# Dash_Switches.net
KiCad netlist of a schematic drawn in EAGLE
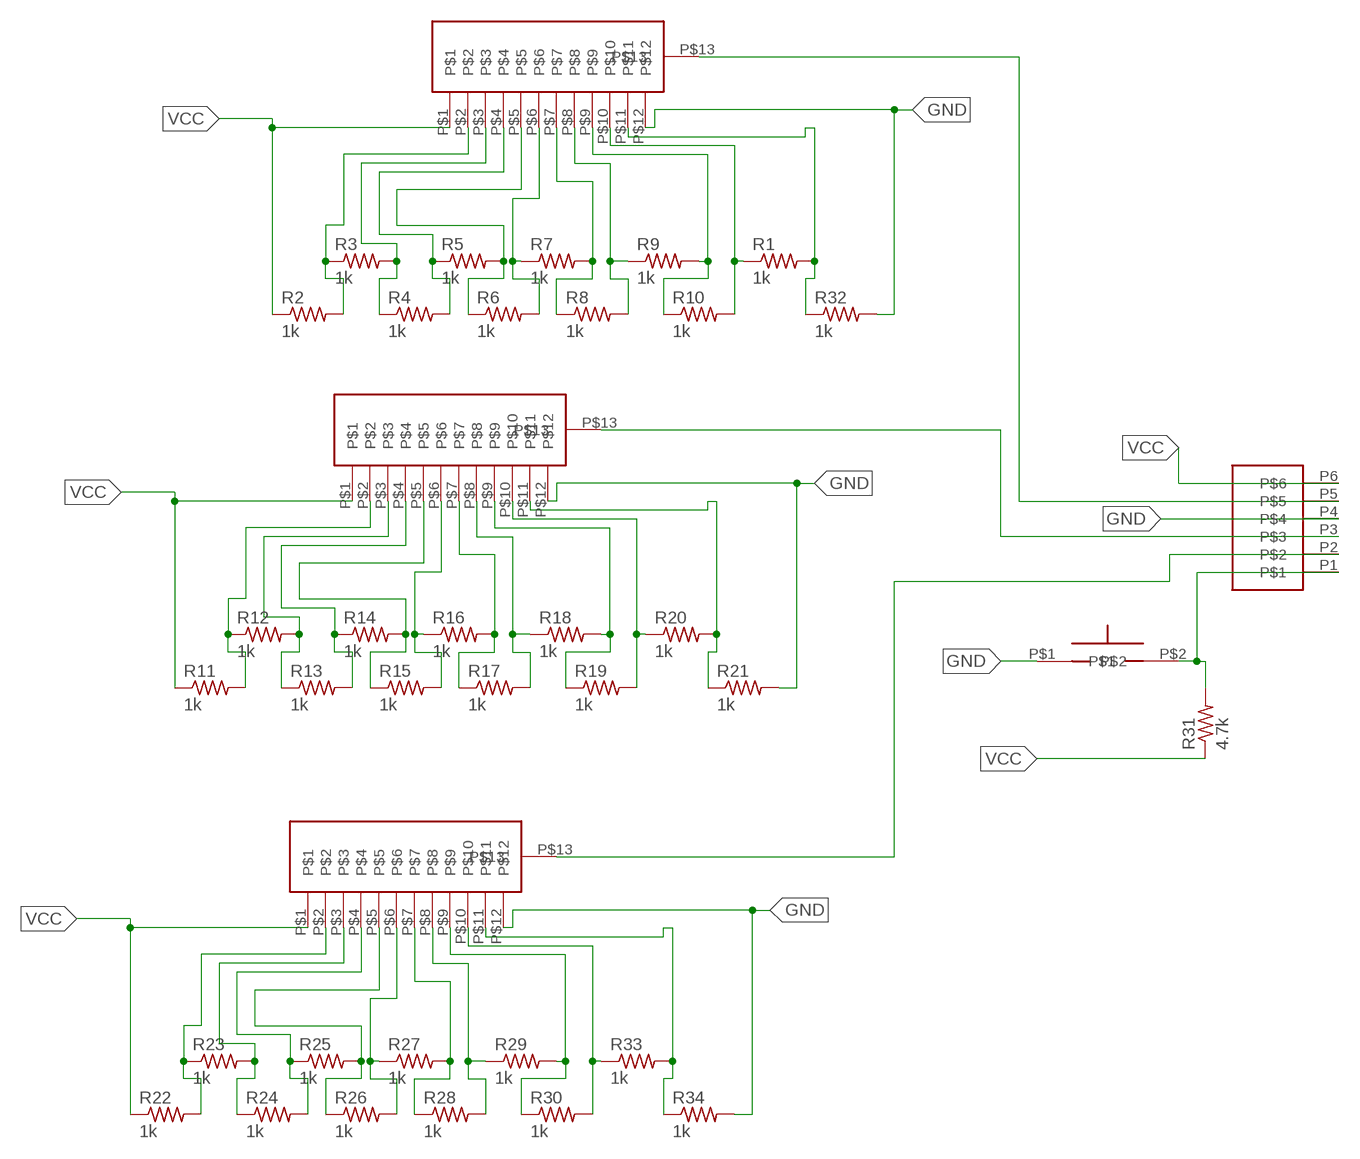
[diagram p0: schematic, sheet 1]

(export (version "E")
  (design (tool "Eeschema 10.0.6"))
  (components
    (comp (ref "R1")
      (value "1k")
      (footprint "eagle-import:R0603")
      (libsource (lib "eagle-import") (part "R-US_R0603"))
    )
    (comp (ref "R2")
      (value "1k")
      (footprint "eagle-import:R0603")
      (libsource (lib "eagle-import") (part "R-US_R0603"))
    )
    (comp (ref "R3")
      (value "1k")
      (footprint "eagle-import:R0603")
      (libsource (lib "eagle-import") (part "R-US_R0603"))
    )
    (comp (ref "R4")
      (value "1k")
      (footprint "eagle-import:R0603")
      (libsource (lib "eagle-import") (part "R-US_R0603"))
    )
    (comp (ref "R5")
      (value "1k")
      (footprint "eagle-import:R0603")
      (libsource (lib "eagle-import") (part "R-US_R0603"))
    )
    (comp (ref "R6")
      (value "1k")
      (footprint "eagle-import:R0603")
      (libsource (lib "eagle-import") (part "R-US_R0603"))
    )
    (comp (ref "R7")
      (value "1k")
      (footprint "eagle-import:R0603")
      (libsource (lib "eagle-import") (part "R-US_R0603"))
    )
    (comp (ref "R8")
      (value "1k")
      (footprint "eagle-import:R0603")
      (libsource (lib "eagle-import") (part "R-US_R0603"))
    )
    (comp (ref "R9")
      (value "1k")
      (footprint "eagle-import:R0603")
      (libsource (lib "eagle-import") (part "R-US_R0603"))
    )
    (comp (ref "R10")
      (value "1k")
      (footprint "eagle-import:R0603")
      (libsource (lib "eagle-import") (part "R-US_R0603"))
    )
    (comp (ref "R11")
      (value "1k")
      (footprint "eagle-import:R0603")
      (libsource (lib "eagle-import") (part "R-US_R0603"))
    )
    (comp (ref "R12")
      (value "1k")
      (footprint "eagle-import:R0603")
      (libsource (lib "eagle-import") (part "R-US_R0603"))
    )
    (comp (ref "R13")
      (value "1k")
      (footprint "eagle-import:R0603")
      (libsource (lib "eagle-import") (part "R-US_R0603"))
    )
    (comp (ref "R14")
      (value "1k")
      (footprint "eagle-import:R0603")
      (libsource (lib "eagle-import") (part "R-US_R0603"))
    )
    (comp (ref "R15")
      (value "1k")
      (footprint "eagle-import:R0603")
      (libsource (lib "eagle-import") (part "R-US_R0603"))
    )
    (comp (ref "R16")
      (value "1k")
      (footprint "eagle-import:R0603")
      (libsource (lib "eagle-import") (part "R-US_R0603"))
    )
    (comp (ref "R17")
      (value "1k")
      (footprint "eagle-import:R0603")
      (libsource (lib "eagle-import") (part "R-US_R0603"))
    )
    (comp (ref "R18")
      (value "1k")
      (footprint "eagle-import:R0603")
      (libsource (lib "eagle-import") (part "R-US_R0603"))
    )
    (comp (ref "R19")
      (value "1k")
      (footprint "eagle-import:R0603")
      (libsource (lib "eagle-import") (part "R-US_R0603"))
    )
    (comp (ref "R20")
      (value "1k")
      (footprint "eagle-import:R0603")
      (libsource (lib "eagle-import") (part "R-US_R0603"))
    )
    (comp (ref "R21")
      (value "1k")
      (footprint "eagle-import:R0603")
      (libsource (lib "eagle-import") (part "R-US_R0603"))
    )
    (comp (ref "R22")
      (value "1k")
      (footprint "eagle-import:R0603")
      (libsource (lib "eagle-import") (part "R-US_R0603"))
    )
    (comp (ref "R23")
      (value "1k")
      (footprint "eagle-import:R0603")
      (libsource (lib "eagle-import") (part "R-US_R0603"))
    )
    (comp (ref "R24")
      (value "1k")
      (footprint "eagle-import:R0603")
      (libsource (lib "eagle-import") (part "R-US_R0603"))
    )
    (comp (ref "R25")
      (value "1k")
      (footprint "eagle-import:R0603")
      (libsource (lib "eagle-import") (part "R-US_R0603"))
    )
    (comp (ref "R26")
      (value "1k")
      (footprint "eagle-import:R0603")
      (libsource (lib "eagle-import") (part "R-US_R0603"))
    )
    (comp (ref "R27")
      (value "1k")
      (footprint "eagle-import:R0603")
      (libsource (lib "eagle-import") (part "R-US_R0603"))
    )
    (comp (ref "R28")
      (value "1k")
      (footprint "eagle-import:R0603")
      (libsource (lib "eagle-import") (part "R-US_R0603"))
    )
    (comp (ref "R29")
      (value "1k")
      (footprint "eagle-import:R0603")
      (libsource (lib "eagle-import") (part "R-US_R0603"))
    )
    (comp (ref "R30")
      (value "1k")
      (footprint "eagle-import:R0603")
      (libsource (lib "eagle-import") (part "R-US_R0603"))
    )
    (comp (ref "R31")
      (value "4.7k")
      (footprint "eagle-import:R0603")
      (libsource (lib "eagle-import") (part "R-US_R0603"))
    )
    (comp (ref "R32")
      (value "1k")
      (footprint "eagle-import:R0603")
      (libsource (lib "eagle-import") (part "R-US_R0603"))
    )
    (comp (ref "R33")
      (value "1k")
      (footprint "eagle-import:R0603")
      (libsource (lib "eagle-import") (part "R-US_R0603"))
    )
    (comp (ref "R34")
      (value "1k")
      (footprint "eagle-import:R0603")
      (libsource (lib "eagle-import") (part "R-US_R0603"))
    )
    (comp (ref "U$1")
      (value "ROTSWITCH")
      (footprint "eagle-import:ROTSWITCH")
      (libsource (lib "eagle-import") (part "ROTSWITCH"))
    )
    (comp (ref "U$2")
      (value "ROTSWITCH")
      (footprint "eagle-import:ROTSWITCH")
      (libsource (lib "eagle-import") (part "ROTSWITCH"))
    )
    (comp (ref "U$3")
      (value "ROTSWITCH")
      (footprint "eagle-import:ROTSWITCH")
      (libsource (lib "eagle-import") (part "ROTSWITCH"))
    )
    (comp (ref "U$5")
      (value "PUSH")
      (footprint "eagle-import:PUSH")
      (libsource (lib "eagle-import") (part "PUSH"))
    )
    (comp (ref "U$6")
      (value "MICRO6LOCK")
      (footprint "eagle-import:MICRO6LOCK")
      (libsource (lib "eagle-import") (part "MICRO6LOCK"))
    )
  )
  (nets
    (net (code "1") (name "GND") (class "Default")
      (node (ref "R21") (pin "2") (pinfunction "2_2") (pintype "passive"))
      (node (ref "R32") (pin "2") (pinfunction "2_2") (pintype "passive"))
      (node (ref "R34") (pin "2") (pinfunction "2_2") (pintype "passive"))
      (node (ref "U$1") (pin "P$12") (pinfunction "P$12_P$12") (pintype "bidirectional"))
      (node (ref "U$2") (pin "P$12") (pinfunction "P$12_P$12") (pintype "bidirectional"))
      (node (ref "U$3") (pin "P$12") (pinfunction "P$12_P$12") (pintype "bidirectional"))
      (node (ref "U$5") (pin "P$1") (pinfunction "P$1_P$1") (pintype "bidirectional"))
      (node (ref "U$6") (pin "P4") (pinfunction "P$4_P4") (pintype "bidirectional"))
    )
    (net (code "2") (name "Net-(R1-Pad1)") (class "Default")
      (node (ref "R1") (pin "1") (pinfunction "1_1") (pintype "passive"))
      (node (ref "R10") (pin "2") (pinfunction "2_2") (pintype "passive"))
      (node (ref "U$1") (pin "P$10") (pinfunction "P$10_P$10") (pintype "bidirectional"))
    )
    (net (code "3") (name "Net-(R1-Pad2)") (class "Default")
      (node (ref "R1") (pin "2") (pinfunction "2_2") (pintype "passive"))
      (node (ref "R32") (pin "1") (pinfunction "1_1") (pintype "passive"))
      (node (ref "U$1") (pin "P$11") (pinfunction "P$11_P$11") (pintype "bidirectional"))
    )
    (net (code "4") (name "Net-(R2-Pad2)") (class "Default")
      (node (ref "R2") (pin "2") (pinfunction "2_2") (pintype "passive"))
      (node (ref "R3") (pin "1") (pinfunction "1_1") (pintype "passive"))
      (node (ref "U$1") (pin "P$2") (pinfunction "P$2_P$2") (pintype "bidirectional"))
    )
    (net (code "5") (name "Net-(R3-Pad2)") (class "Default")
      (node (ref "R3") (pin "2") (pinfunction "2_2") (pintype "passive"))
      (node (ref "R4") (pin "1") (pinfunction "1_1") (pintype "passive"))
      (node (ref "U$1") (pin "P$3") (pinfunction "P$3_P$3") (pintype "bidirectional"))
    )
    (net (code "6") (name "Net-(R4-Pad2)") (class "Default")
      (node (ref "R4") (pin "2") (pinfunction "2_2") (pintype "passive"))
      (node (ref "R5") (pin "1") (pinfunction "1_1") (pintype "passive"))
      (node (ref "U$1") (pin "P$4") (pinfunction "P$4_P$4") (pintype "bidirectional"))
    )
    (net (code "7") (name "Net-(R5-Pad2)") (class "Default")
      (node (ref "R5") (pin "2") (pinfunction "2_2") (pintype "passive"))
      (node (ref "R6") (pin "1") (pinfunction "1_1") (pintype "passive"))
      (node (ref "U$1") (pin "P$5") (pinfunction "P$5_P$5") (pintype "bidirectional"))
    )
    (net (code "8") (name "Net-(R6-Pad2)") (class "Default")
      (node (ref "R6") (pin "2") (pinfunction "2_2") (pintype "passive"))
      (node (ref "R7") (pin "1") (pinfunction "1_1") (pintype "passive"))
      (node (ref "U$1") (pin "P$6") (pinfunction "P$6_P$6") (pintype "bidirectional"))
    )
    (net (code "9") (name "Net-(R7-Pad2)") (class "Default")
      (node (ref "R7") (pin "2") (pinfunction "2_2") (pintype "passive"))
      (node (ref "R8") (pin "1") (pinfunction "1_1") (pintype "passive"))
      (node (ref "U$1") (pin "P$7") (pinfunction "P$7_P$7") (pintype "bidirectional"))
    )
    (net (code "10") (name "Net-(R8-Pad2)") (class "Default")
      (node (ref "R8") (pin "2") (pinfunction "2_2") (pintype "passive"))
      (node (ref "R9") (pin "1") (pinfunction "1_1") (pintype "passive"))
      (node (ref "U$1") (pin "P$8") (pinfunction "P$8_P$8") (pintype "bidirectional"))
    )
    (net (code "11") (name "Net-(R10-Pad1)") (class "Default")
      (node (ref "R10") (pin "1") (pinfunction "1_1") (pintype "passive"))
      (node (ref "R9") (pin "2") (pinfunction "2_2") (pintype "passive"))
      (node (ref "U$1") (pin "P$9") (pinfunction "P$9_P$9") (pintype "bidirectional"))
    )
    (net (code "12") (name "Net-(R11-Pad2)") (class "Default")
      (node (ref "R11") (pin "2") (pinfunction "2_2") (pintype "passive"))
      (node (ref "R12") (pin "1") (pinfunction "1_1") (pintype "passive"))
      (node (ref "U$2") (pin "P$2") (pinfunction "P$2_P$2") (pintype "bidirectional"))
    )
    (net (code "13") (name "Net-(R12-Pad2)") (class "Default")
      (node (ref "R12") (pin "2") (pinfunction "2_2") (pintype "passive"))
      (node (ref "R13") (pin "1") (pinfunction "1_1") (pintype "passive"))
      (node (ref "U$2") (pin "P$3") (pinfunction "P$3_P$3") (pintype "bidirectional"))
    )
    (net (code "14") (name "Net-(R13-Pad2)") (class "Default")
      (node (ref "R13") (pin "2") (pinfunction "2_2") (pintype "passive"))
      (node (ref "R14") (pin "1") (pinfunction "1_1") (pintype "passive"))
      (node (ref "U$2") (pin "P$4") (pinfunction "P$4_P$4") (pintype "bidirectional"))
    )
    (net (code "15") (name "Net-(R14-Pad2)") (class "Default")
      (node (ref "R14") (pin "2") (pinfunction "2_2") (pintype "passive"))
      (node (ref "R15") (pin "1") (pinfunction "1_1") (pintype "passive"))
      (node (ref "U$2") (pin "P$5") (pinfunction "P$5_P$5") (pintype "bidirectional"))
    )
    (net (code "16") (name "Net-(R15-Pad2)") (class "Default")
      (node (ref "R15") (pin "2") (pinfunction "2_2") (pintype "passive"))
      (node (ref "R16") (pin "1") (pinfunction "1_1") (pintype "passive"))
      (node (ref "U$2") (pin "P$6") (pinfunction "P$6_P$6") (pintype "bidirectional"))
    )
    (net (code "17") (name "Net-(R16-Pad2)") (class "Default")
      (node (ref "R16") (pin "2") (pinfunction "2_2") (pintype "passive"))
      (node (ref "R17") (pin "1") (pinfunction "1_1") (pintype "passive"))
      (node (ref "U$2") (pin "P$7") (pinfunction "P$7_P$7") (pintype "bidirectional"))
    )
    (net (code "18") (name "Net-(R17-Pad2)") (class "Default")
      (node (ref "R17") (pin "2") (pinfunction "2_2") (pintype "passive"))
      (node (ref "R18") (pin "1") (pinfunction "1_1") (pintype "passive"))
      (node (ref "U$2") (pin "P$8") (pinfunction "P$8_P$8") (pintype "bidirectional"))
    )
    (net (code "19") (name "Net-(R18-Pad2)") (class "Default")
      (node (ref "R18") (pin "2") (pinfunction "2_2") (pintype "passive"))
      (node (ref "R19") (pin "1") (pinfunction "1_1") (pintype "passive"))
      (node (ref "U$2") (pin "P$9") (pinfunction "P$9_P$9") (pintype "bidirectional"))
    )
    (net (code "20") (name "Net-(R19-Pad2)") (class "Default")
      (node (ref "R19") (pin "2") (pinfunction "2_2") (pintype "passive"))
      (node (ref "R20") (pin "1") (pinfunction "1_1") (pintype "passive"))
      (node (ref "U$2") (pin "P$10") (pinfunction "P$10_P$10") (pintype "bidirectional"))
    )
    (net (code "21") (name "Net-(R20-Pad2)") (class "Default")
      (node (ref "R20") (pin "2") (pinfunction "2_2") (pintype "passive"))
      (node (ref "R21") (pin "1") (pinfunction "1_1") (pintype "passive"))
      (node (ref "U$2") (pin "P$11") (pinfunction "P$11_P$11") (pintype "bidirectional"))
    )
    (net (code "22") (name "Net-(R22-Pad2)") (class "Default")
      (node (ref "R22") (pin "2") (pinfunction "2_2") (pintype "passive"))
      (node (ref "R23") (pin "1") (pinfunction "1_1") (pintype "passive"))
      (node (ref "U$3") (pin "P$2") (pinfunction "P$2_P$2") (pintype "bidirectional"))
    )
    (net (code "23") (name "Net-(R23-Pad2)") (class "Default")
      (node (ref "R23") (pin "2") (pinfunction "2_2") (pintype "passive"))
      (node (ref "R24") (pin "1") (pinfunction "1_1") (pintype "passive"))
      (node (ref "U$3") (pin "P$3") (pinfunction "P$3_P$3") (pintype "bidirectional"))
    )
    (net (code "24") (name "Net-(R24-Pad2)") (class "Default")
      (node (ref "R24") (pin "2") (pinfunction "2_2") (pintype "passive"))
      (node (ref "R25") (pin "1") (pinfunction "1_1") (pintype "passive"))
      (node (ref "U$3") (pin "P$4") (pinfunction "P$4_P$4") (pintype "bidirectional"))
    )
    (net (code "25") (name "Net-(R25-Pad2)") (class "Default")
      (node (ref "R25") (pin "2") (pinfunction "2_2") (pintype "passive"))
      (node (ref "R26") (pin "1") (pinfunction "1_1") (pintype "passive"))
      (node (ref "U$3") (pin "P$5") (pinfunction "P$5_P$5") (pintype "bidirectional"))
    )
    (net (code "26") (name "Net-(R26-Pad2)") (class "Default")
      (node (ref "R26") (pin "2") (pinfunction "2_2") (pintype "passive"))
      (node (ref "R27") (pin "1") (pinfunction "1_1") (pintype "passive"))
      (node (ref "U$3") (pin "P$6") (pinfunction "P$6_P$6") (pintype "bidirectional"))
    )
    (net (code "27") (name "Net-(R27-Pad2)") (class "Default")
      (node (ref "R27") (pin "2") (pinfunction "2_2") (pintype "passive"))
      (node (ref "R28") (pin "1") (pinfunction "1_1") (pintype "passive"))
      (node (ref "U$3") (pin "P$7") (pinfunction "P$7_P$7") (pintype "bidirectional"))
    )
    (net (code "28") (name "Net-(R28-Pad2)") (class "Default")
      (node (ref "R28") (pin "2") (pinfunction "2_2") (pintype "passive"))
      (node (ref "R29") (pin "1") (pinfunction "1_1") (pintype "passive"))
      (node (ref "U$3") (pin "P$8") (pinfunction "P$8_P$8") (pintype "bidirectional"))
    )
    (net (code "29") (name "Net-(R29-Pad2)") (class "Default")
      (node (ref "R29") (pin "2") (pinfunction "2_2") (pintype "passive"))
      (node (ref "R30") (pin "1") (pinfunction "1_1") (pintype "passive"))
      (node (ref "U$3") (pin "P$9") (pinfunction "P$9_P$9") (pintype "bidirectional"))
    )
    (net (code "30") (name "Net-(R30-Pad2)") (class "Default")
      (node (ref "R30") (pin "2") (pinfunction "2_2") (pintype "passive"))
      (node (ref "R33") (pin "1") (pinfunction "1_1") (pintype "passive"))
      (node (ref "U$3") (pin "P$10") (pinfunction "P$10_P$10") (pintype "bidirectional"))
    )
    (net (code "31") (name "Net-(R33-Pad2)") (class "Default")
      (node (ref "R33") (pin "2") (pinfunction "2_2") (pintype "passive"))
      (node (ref "R34") (pin "1") (pinfunction "1_1") (pintype "passive"))
      (node (ref "U$3") (pin "P$11") (pinfunction "P$11_P$11") (pintype "bidirectional"))
    )
    (net (code "32") (name "Net-(U$6-P$1)") (class "Default")
      (node (ref "R31") (pin "2") (pinfunction "2_2") (pintype "passive"))
      (node (ref "U$5") (pin "P$2") (pinfunction "P$2_P$2") (pintype "bidirectional"))
      (node (ref "U$6") (pin "P1") (pinfunction "P$1_P1") (pintype "bidirectional"))
    )
    (net (code "33") (name "Net-(U$6-P$2)") (class "Default")
      (node (ref "U$3") (pin "P$13") (pinfunction "P$13_P$13") (pintype "bidirectional"))
      (node (ref "U$6") (pin "P2") (pinfunction "P$2_P2") (pintype "bidirectional"))
    )
    (net (code "34") (name "Net-(U$6-P$3)") (class "Default")
      (node (ref "U$2") (pin "P$13") (pinfunction "P$13_P$13") (pintype "bidirectional"))
      (node (ref "U$6") (pin "P3") (pinfunction "P$3_P3") (pintype "bidirectional"))
    )
    (net (code "35") (name "Net-(U$6-P$5)") (class "Default")
      (node (ref "U$1") (pin "P$13") (pinfunction "P$13_P$13") (pintype "bidirectional"))
      (node (ref "U$6") (pin "P5") (pinfunction "P$5_P5") (pintype "bidirectional"))
    )
    (net (code "36") (name "VCC") (class "Default")
      (node (ref "R11") (pin "1") (pinfunction "1_1") (pintype "passive"))
      (node (ref "R2") (pin "1") (pinfunction "1_1") (pintype "passive"))
      (node (ref "R22") (pin "1") (pinfunction "1_1") (pintype "passive"))
      (node (ref "R31") (pin "1") (pinfunction "1_1") (pintype "passive"))
      (node (ref "U$1") (pin "P$1") (pinfunction "P$1_P$1") (pintype "bidirectional"))
      (node (ref "U$2") (pin "P$1") (pinfunction "P$1_P$1") (pintype "bidirectional"))
      (node (ref "U$3") (pin "P$1") (pinfunction "P$1_P$1") (pintype "bidirectional"))
      (node (ref "U$6") (pin "P6") (pinfunction "P$6_P6") (pintype "bidirectional"))
    )
  )
)
